# design.net
KiCad netlist of a schematic drawn in EAGLE
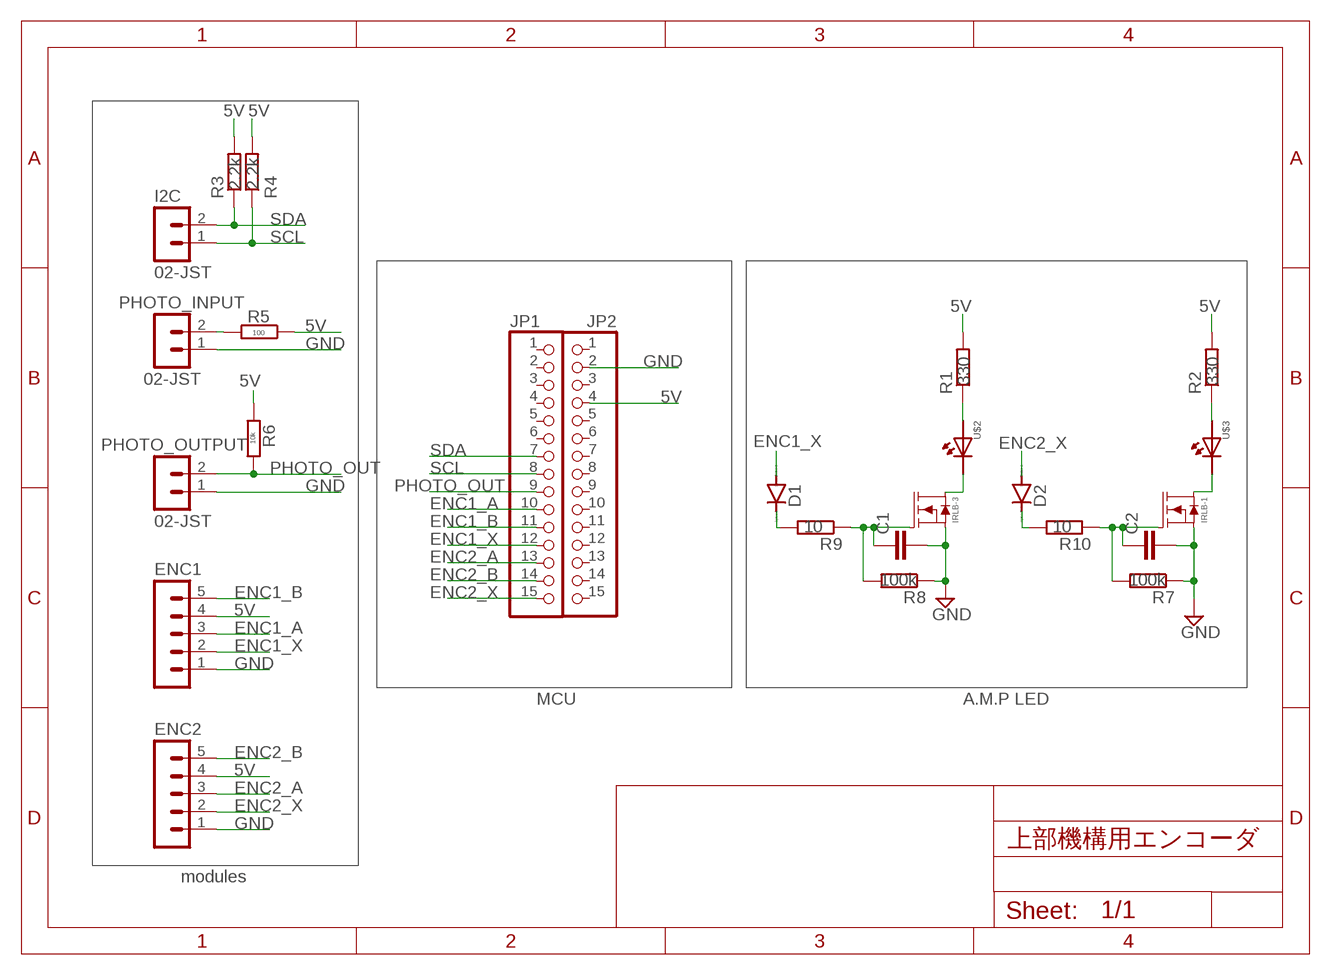
[diagram p0: schematic, sheet 1]

(export (version "E")
  (design (tool "Eeschema 10.0.6"))
  (components
    (comp (ref "C1")
      (value "C5/2.5")
      (footprint "eagle-import:C5B2.5")
      (libsource (lib "eagle-import") (part "C5/2.5"))
    )
    (comp (ref "C2")
      (value "C5/2.5")
      (footprint "eagle-import:C5B2.5")
      (libsource (lib "eagle-import") (part "C5/2.5"))
    )
    (comp (ref "D1")
      (value "DIODE_STAND")
      (footprint "eagle-import:DIODE_STAND")
      (libsource (lib "eagle-import") (part "DIODE_STAND"))
    )
    (comp (ref "D2")
      (value "DIODE_STAND")
      (footprint "eagle-import:DIODE_STAND")
      (libsource (lib "eagle-import") (part "DIODE_STAND"))
    )
    (comp (ref "ENC1")
      (value "05-JST")
      (footprint "eagle-import:B5B-XH")
      (libsource (lib "eagle-import") (part "05-JST"))
    )
    (comp (ref "ENC2")
      (value "05-JST")
      (footprint "eagle-import:B5B-XH")
      (libsource (lib "eagle-import") (part "05-JST"))
    )
    (comp (ref "I2C")
      (value "02-JST")
      (footprint "eagle-import:B2B-XH")
      (libsource (lib "eagle-import") (part "02-JST"))
    )
    (comp (ref "IRLB-1")
      (value "IRLB3813STAND")
      (footprint "eagle-import:TO-220AB-STAND")
      (libsource (lib "eagle-import") (part "IRLB3813STAND"))
    )
    (comp (ref "IRLB-3")
      (value "IRLB3813STAND")
      (footprint "eagle-import:TO-220AB-STAND")
      (libsource (lib "eagle-import") (part "IRLB3813STAND"))
    )
    (comp (ref "JP1")
      (value "PINHD-1X15")
      (footprint "eagle-import:1X15")
      (libsource (lib "eagle-import") (part "PINHD-1X15"))
    )
    (comp (ref "JP2")
      (value "PINHD-1X15")
      (footprint "eagle-import:1X15")
      (libsource (lib "eagle-import") (part "PINHD-1X15"))
    )
    (comp (ref "PHOTO_INPUT")
      (value "02-JST")
      (footprint "eagle-import:B2B-XH")
      (libsource (lib "eagle-import") (part "02-JST"))
    )
    (comp (ref "PHOTO_OUTPUT")
      (value "02-JST")
      (footprint "eagle-import:B2B-XH")
      (libsource (lib "eagle-import") (part "02-JST"))
    )
    (comp (ref "R1")
      (value "330")
      (footprint "eagle-import:0207_2V")
      (libsource (lib "eagle-import") (part "R-EU_0207/2V"))
    )
    (comp (ref "R2")
      (value "330")
      (footprint "eagle-import:0207_2V")
      (libsource (lib "eagle-import") (part "R-EU_0207/2V"))
    )
    (comp (ref "R3")
      (value "2.2k")
      (footprint "eagle-import:0207_2V")
      (libsource (lib "eagle-import") (part "R-EU_0207/2V"))
    )
    (comp (ref "R4")
      (value "2.2k")
      (footprint "eagle-import:0207_2V")
      (libsource (lib "eagle-import") (part "R-EU_0207/2V"))
    )
    (comp (ref "R5")
      (value "100")
      (footprint "eagle-import:0204_7")
      (libsource (lib "eagle-import") (part "R-EU_0204/7"))
    )
    (comp (ref "R6")
      (value "10k")
      (footprint "eagle-import:0204_7")
      (libsource (lib "eagle-import") (part "R-EU_0204/7"))
    )
    (comp (ref "R7")
      (value "100k")
      (footprint "eagle-import:0207_2V")
      (libsource (lib "eagle-import") (part "R-EU_0207/2V"))
    )
    (comp (ref "R8")
      (value "100k")
      (footprint "eagle-import:0207_2V")
      (libsource (lib "eagle-import") (part "R-EU_0207/2V"))
    )
    (comp (ref "R9")
      (value "10")
      (footprint "eagle-import:0207_2V")
      (libsource (lib "eagle-import") (part "R-EU_0207/2V"))
    )
    (comp (ref "R10")
      (value "10")
      (footprint "eagle-import:0207_2V")
      (libsource (lib "eagle-import") (part "R-EU_0207/2V"))
    )
    (comp (ref "U$2")
      (value "LED")
      (footprint "eagle-import:LED3MM")
      (libsource (lib "eagle-import") (part "LED"))
    )
    (comp (ref "U$3")
      (value "LED")
      (footprint "eagle-import:LED3MM")
      (libsource (lib "eagle-import") (part "LED"))
    )
  )
  (nets
    (net (code "1") (name "/5V") (class "Default")
      (node (ref "ENC1") (pin "4") (pinfunction "4_4") (pintype "passive"))
      (node (ref "ENC2") (pin "4") (pinfunction "4_4") (pintype "passive"))
      (node (ref "JP2") (pin "4") (pinfunction "4_4") (pintype "passive"))
      (node (ref "R1") (pin "2") (pinfunction "2_2") (pintype "passive"))
      (node (ref "R2") (pin "2") (pinfunction "2_2") (pintype "passive"))
      (node (ref "R3") (pin "2") (pinfunction "2_2") (pintype "passive"))
      (node (ref "R4") (pin "2") (pinfunction "2_2") (pintype "passive"))
      (node (ref "R5") (pin "1") (pinfunction "1_1") (pintype "passive"))
      (node (ref "R6") (pin "2") (pinfunction "2_2") (pintype "passive"))
    )
    (net (code "2") (name "/ENC1_A") (class "Default")
      (node (ref "ENC1") (pin "3") (pinfunction "3_3") (pintype "passive"))
      (node (ref "JP1") (pin "10") (pinfunction "10_10") (pintype "passive"))
    )
    (net (code "3") (name "/ENC1_B") (class "Default")
      (node (ref "ENC1") (pin "5") (pinfunction "5_5") (pintype "passive"))
      (node (ref "JP1") (pin "11") (pinfunction "11_11") (pintype "passive"))
    )
    (net (code "4") (name "/ENC1_X") (class "Default")
      (node (ref "D1") (pin "A") (pinfunction "A_A") (pintype "passive"))
      (node (ref "ENC1") (pin "2") (pinfunction "2_2") (pintype "passive"))
      (node (ref "JP1") (pin "12") (pinfunction "12_12") (pintype "passive"))
    )
    (net (code "5") (name "/ENC2_A") (class "Default")
      (node (ref "ENC2") (pin "3") (pinfunction "3_3") (pintype "passive"))
      (node (ref "JP1") (pin "13") (pinfunction "13_13") (pintype "passive"))
    )
    (net (code "6") (name "/ENC2_B") (class "Default")
      (node (ref "ENC2") (pin "5") (pinfunction "5_5") (pintype "passive"))
      (node (ref "JP1") (pin "14") (pinfunction "14_14") (pintype "passive"))
    )
    (net (code "7") (name "/ENC2_X") (class "Default")
      (node (ref "D2") (pin "A") (pinfunction "A_A") (pintype "passive"))
      (node (ref "ENC2") (pin "2") (pinfunction "2_2") (pintype "passive"))
      (node (ref "JP1") (pin "15") (pinfunction "15_15") (pintype "passive"))
    )
    (net (code "8") (name "/PHOTO_OUT") (class "Default")
      (node (ref "JP1") (pin "9") (pinfunction "9_9") (pintype "passive"))
      (node (ref "PHOTO_OUTPUT") (pin "2") (pinfunction "2_2") (pintype "passive"))
      (node (ref "R6") (pin "1") (pinfunction "1_1") (pintype "passive"))
    )
    (net (code "9") (name "/SCL") (class "Default")
      (node (ref "I2C") (pin "1") (pinfunction "1_1") (pintype "passive"))
      (node (ref "JP1") (pin "8") (pinfunction "8_8") (pintype "passive"))
      (node (ref "R4") (pin "1") (pinfunction "1_1") (pintype "passive"))
    )
    (net (code "10") (name "/SDA") (class "Default")
      (node (ref "I2C") (pin "2") (pinfunction "2_2") (pintype "passive"))
      (node (ref "JP1") (pin "7") (pinfunction "7_7") (pintype "passive"))
      (node (ref "R3") (pin "1") (pinfunction "1_1") (pintype "passive"))
    )
    (net (code "11") (name "GND") (class "Default")
      (node (ref "C1") (pin "2") (pinfunction "2_2") (pintype "passive"))
      (node (ref "C2") (pin "2") (pinfunction "2_2") (pintype "passive"))
      (node (ref "ENC1") (pin "1") (pinfunction "1_1") (pintype "passive"))
      (node (ref "ENC2") (pin "1") (pinfunction "1_1") (pintype "passive"))
      (node (ref "IRLB-1") (pin "S") (pinfunction "S_S") (pintype "passive"))
      (node (ref "IRLB-3") (pin "S") (pinfunction "S_S") (pintype "passive"))
      (node (ref "JP2") (pin "2") (pinfunction "2_2") (pintype "passive"))
      (node (ref "PHOTO_INPUT") (pin "1") (pinfunction "1_1") (pintype "passive"))
      (node (ref "PHOTO_OUTPUT") (pin "1") (pinfunction "1_1") (pintype "passive"))
      (node (ref "R7") (pin "1") (pinfunction "1_1") (pintype "passive"))
      (node (ref "R8") (pin "1") (pinfunction "1_1") (pintype "passive"))
    )
    (net (code "12") (name "Net-(C1-Pad1)") (class "Default")
      (node (ref "C1") (pin "1") (pinfunction "1_1") (pintype "passive"))
      (node (ref "IRLB-3") (pin "G") (pinfunction "G_G") (pintype "passive"))
      (node (ref "R8") (pin "2") (pinfunction "2_2") (pintype "passive"))
      (node (ref "R9") (pin "1") (pinfunction "1_1") (pintype "passive"))
    )
    (net (code "13") (name "Net-(C2-Pad1)") (class "Default")
      (node (ref "C2") (pin "1") (pinfunction "1_1") (pintype "passive"))
      (node (ref "IRLB-1") (pin "G") (pinfunction "G_G") (pintype "passive"))
      (node (ref "R10") (pin "1") (pinfunction "1_1") (pintype "passive"))
      (node (ref "R7") (pin "2") (pinfunction "2_2") (pintype "passive"))
    )
    (net (code "14") (name "Net-(D1-PadC)") (class "Default")
      (node (ref "D1") (pin "C") (pinfunction "C_C") (pintype "passive"))
      (node (ref "R9") (pin "2") (pinfunction "2_2") (pintype "passive"))
    )
    (net (code "15") (name "Net-(D2-PadC)") (class "Default")
      (node (ref "D2") (pin "C") (pinfunction "C_C") (pintype "passive"))
      (node (ref "R10") (pin "2") (pinfunction "2_2") (pintype "passive"))
    )
    (net (code "16") (name "Net-(IRLB-1-PadD)") (class "Default")
      (node (ref "IRLB-1") (pin "D") (pinfunction "D_D") (pintype "passive"))
      (node (ref "U$3") (pin "C") (pinfunction "C_C") (pintype "passive"))
    )
    (net (code "17") (name "Net-(IRLB-3-PadD)") (class "Default")
      (node (ref "IRLB-3") (pin "D") (pinfunction "D_D") (pintype "passive"))
      (node (ref "U$2") (pin "C") (pinfunction "C_C") (pintype "passive"))
    )
    (net (code "18") (name "Net-(PHOTO_INPUT-Pad2)") (class "Default")
      (node (ref "PHOTO_INPUT") (pin "2") (pinfunction "2_2") (pintype "passive"))
      (node (ref "R5") (pin "2") (pinfunction "2_2") (pintype "passive"))
    )
    (net (code "19") (name "Net-(R1-Pad1)") (class "Default")
      (node (ref "R1") (pin "1") (pinfunction "1_1") (pintype "passive"))
      (node (ref "U$2") (pin "A") (pinfunction "A_A") (pintype "passive"))
    )
    (net (code "20") (name "Net-(R2-Pad1)") (class "Default")
      (node (ref "R2") (pin "1") (pinfunction "1_1") (pintype "passive"))
      (node (ref "U$3") (pin "A") (pinfunction "A_A") (pintype "passive"))
    )
    (net (code "21") (name "unconnected-(JP1-Pad1)") (class "Default")
      (node (ref "JP1") (pin "1") (pinfunction "1_1") (pintype "passive"))
    )
    (net (code "22") (name "unconnected-(JP1-Pad2)") (class "Default")
      (node (ref "JP1") (pin "2") (pinfunction "2_2") (pintype "passive"))
    )
    (net (code "23") (name "unconnected-(JP1-Pad3)") (class "Default")
      (node (ref "JP1") (pin "3") (pinfunction "3_3") (pintype "passive"))
    )
    (net (code "24") (name "unconnected-(JP1-Pad4)") (class "Default")
      (node (ref "JP1") (pin "4") (pinfunction "4_4") (pintype "passive"))
    )
    (net (code "25") (name "unconnected-(JP1-Pad5)") (class "Default")
      (node (ref "JP1") (pin "5") (pinfunction "5_5") (pintype "passive"))
    )
    (net (code "26") (name "unconnected-(JP1-Pad6)") (class "Default")
      (node (ref "JP1") (pin "6") (pinfunction "6_6") (pintype "passive"))
    )
    (net (code "27") (name "unconnected-(JP2-Pad1)") (class "Default")
      (node (ref "JP2") (pin "1") (pinfunction "1_1") (pintype "passive"))
    )
    (net (code "28") (name "unconnected-(JP2-Pad3)") (class "Default")
      (node (ref "JP2") (pin "3") (pinfunction "3_3") (pintype "passive"))
    )
    (net (code "29") (name "unconnected-(JP2-Pad5)") (class "Default")
      (node (ref "JP2") (pin "5") (pinfunction "5_5") (pintype "passive"))
    )
    (net (code "30") (name "unconnected-(JP2-Pad6)") (class "Default")
      (node (ref "JP2") (pin "6") (pinfunction "6_6") (pintype "passive"))
    )
    (net (code "31") (name "unconnected-(JP2-Pad7)") (class "Default")
      (node (ref "JP2") (pin "7") (pinfunction "7_7") (pintype "passive"))
    )
    (net (code "32") (name "unconnected-(JP2-Pad8)") (class "Default")
      (node (ref "JP2") (pin "8") (pinfunction "8_8") (pintype "passive"))
    )
    (net (code "33") (name "unconnected-(JP2-Pad9)") (class "Default")
      (node (ref "JP2") (pin "9") (pinfunction "9_9") (pintype "passive"))
    )
    (net (code "34") (name "unconnected-(JP2-Pad10)") (class "Default")
      (node (ref "JP2") (pin "10") (pinfunction "10_10") (pintype "passive"))
    )
    (net (code "35") (name "unconnected-(JP2-Pad11)") (class "Default")
      (node (ref "JP2") (pin "11") (pinfunction "11_11") (pintype "passive"))
    )
    (net (code "36") (name "unconnected-(JP2-Pad12)") (class "Default")
      (node (ref "JP2") (pin "12") (pinfunction "12_12") (pintype "passive"))
    )
    (net (code "37") (name "unconnected-(JP2-Pad13)") (class "Default")
      (node (ref "JP2") (pin "13") (pinfunction "13_13") (pintype "passive"))
    )
    (net (code "38") (name "unconnected-(JP2-Pad14)") (class "Default")
      (node (ref "JP2") (pin "14") (pinfunction "14_14") (pintype "passive"))
    )
    (net (code "39") (name "unconnected-(JP2-Pad15)") (class "Default")
      (node (ref "JP2") (pin "15") (pinfunction "15_15") (pintype "passive"))
    )
  )
)
